# dcb_lite_logic.net
KiCad netlist of a schematic drawn in Altium Designer
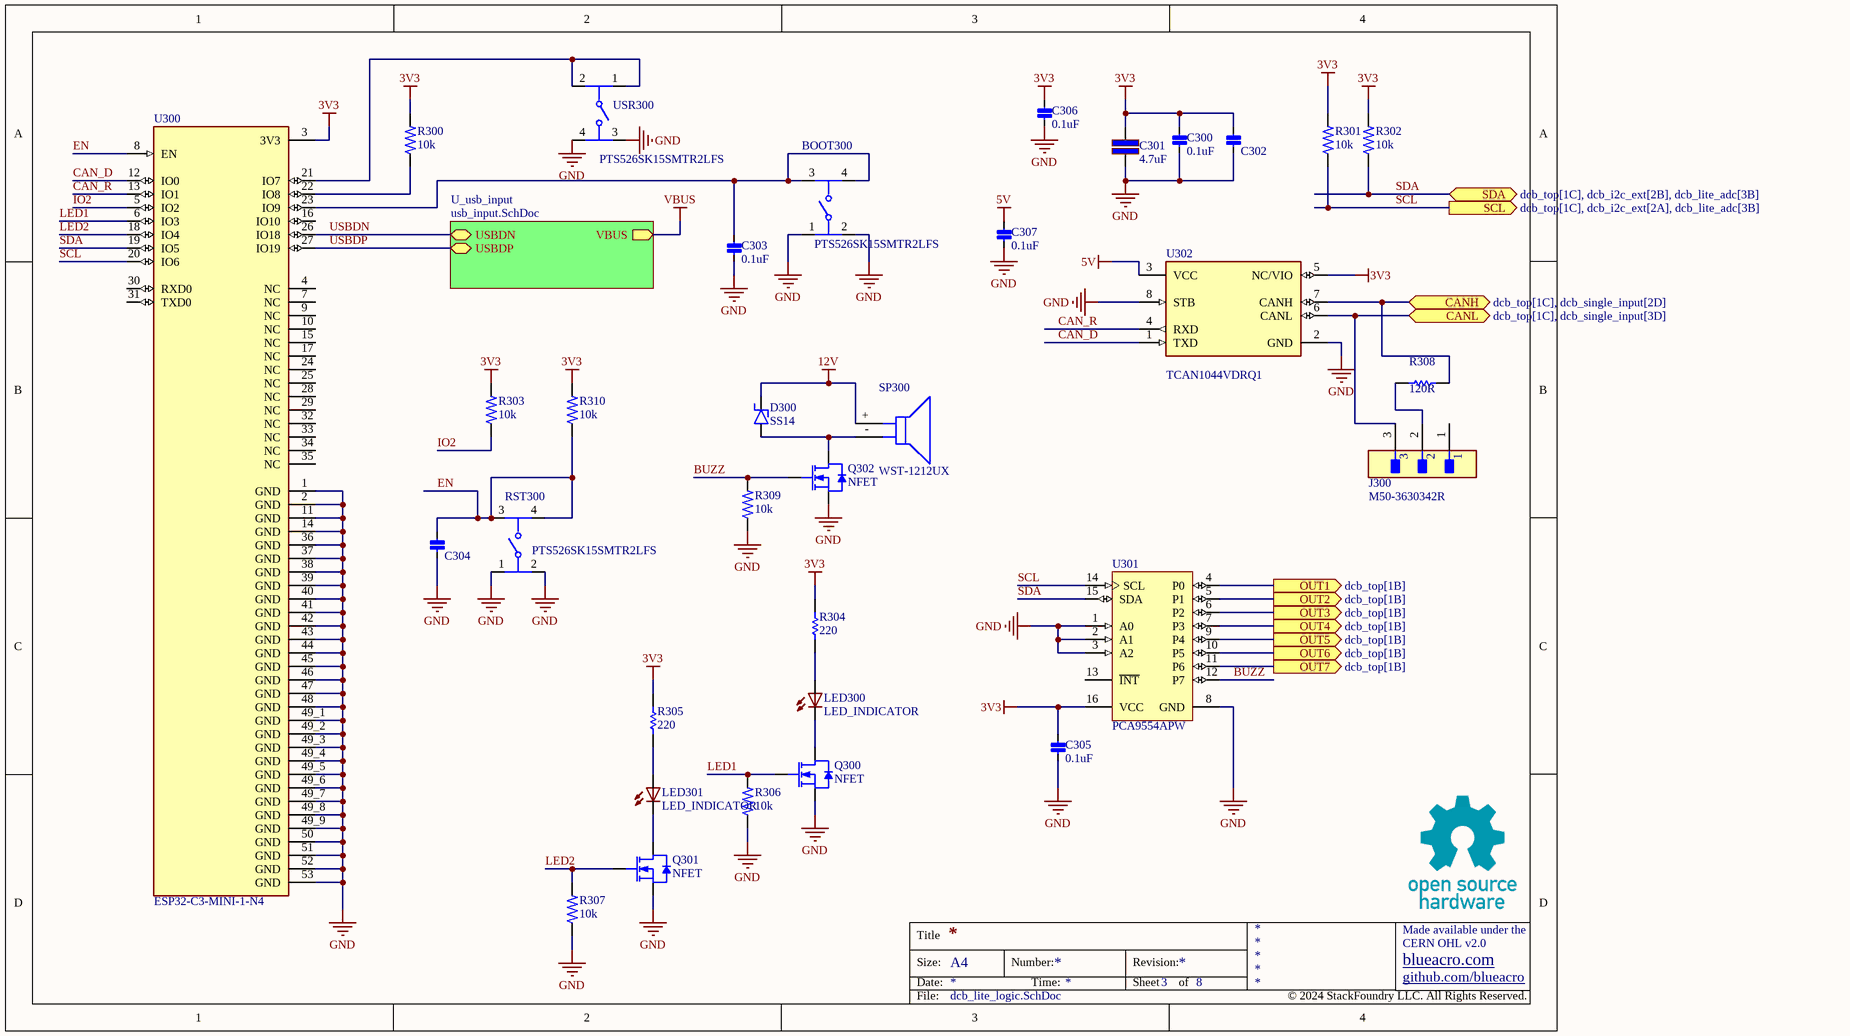
[diagram p0: dcb_lite_logic.SchDoc]

(export (version "E")
  (design (tool "Eeschema 10.0.6"))
  (components
    (comp (ref "BOOT300")
      (value "PTS526SK15SMTR2LFS")
      (footprint "FP-PTS526SK15SMTR2LFS-MFG")
      (description "Switch Tactile N.O. SPST Round Button Gull Wing 0.05A 12VDC 200000Cycles 2.45N SMD T/R")
      (libsource (lib "StackFoundry LLC") (part "b8895f3f4cefb76e1819d2863dba89b"))
    )
    (comp (ref "C300")
      (value "0.1uF")
      (footprint "FP-CL10-IPC_B")
      (description "Cap Ceramic 0.1uF 50V X7R 20% SMD 0603 125C Paper T/R")
      (fields (field (name "VOLTAGE") "50V") (field (name "Comment") "CAP 0.1uF 50V X7R 0603"))
      (libsource (lib "StackFoundry LLC") (part "C-EU"))
    )
    (comp (ref "C301")
      (value "4.7uF")
      (footprint "CAPC3225X20N")
      (description "CAP CER 4.7UF 50V X7R 1210")
      (fields (field (name "VOLTAGE") "50V") (field (name "TOLERANCE") "10%"))
      (libsource (lib "StackFoundry LLC") (part "4.7uF"))
    )
    (comp (ref "C302")
      (value "CAP 1uF 10V X7R 0603")
      (footprint "FP-CL10-IPC_B")
      (description "Cap Ceramic 1uF 10V X7R 10% SMD 0603 125C Paper T/R")
      (libsource (lib "StackFoundry LLC") (part "C-EU"))
    )
    (comp (ref "C303")
      (value "0.1uF")
      (footprint "FP-CL10-IPC_B")
      (description "Cap Ceramic 0.1uF 50V X7R 20% SMD 0603 125C Paper T/R")
      (fields (field (name "VOLTAGE") "50V") (field (name "Comment") "CAP 0.1uF 50V X7R 0603"))
      (libsource (lib "StackFoundry LLC") (part "C-EU"))
    )
    (comp (ref "C304")
      (value "CAP 1uF 10V X7R 0603")
      (footprint "FP-CL10-IPC_B")
      (description "Cap Ceramic 1uF 10V X7R 10% SMD 0603 125C Paper T/R")
      (libsource (lib "StackFoundry LLC") (part "C-EU"))
    )
    (comp (ref "C305")
      (value "0.1uF")
      (footprint "FP-CL10-IPC_B")
      (description "Cap Ceramic 0.1uF 50V X7R 20% SMD 0603 125C Paper T/R")
      (fields (field (name "VOLTAGE") "50V") (field (name "Comment") "CAP 0.1uF 50V X7R 0603"))
      (libsource (lib "StackFoundry LLC") (part "C-EU"))
    )
    (comp (ref "C306")
      (value "0.1uF")
      (footprint "FP-CL10-IPC_B")
      (description "Cap Ceramic 0.1uF 50V X7R 20% SMD 0603 125C Paper T/R")
      (fields (field (name "VOLTAGE") "50V") (field (name "Comment") "CAP 0.1uF 50V X7R 0603"))
      (libsource (lib "StackFoundry LLC") (part "C-EU"))
    )
    (comp (ref "C307")
      (value "0.1uF")
      (footprint "FP-CL10-IPC_B")
      (description "Cap Ceramic 0.1uF 50V X7R 20% SMD 0603 125C Paper T/R")
      (fields (field (name "VOLTAGE") "50V") (field (name "Comment") "CAP 0.1uF 50V X7R 0603"))
      (libsource (lib "StackFoundry LLC") (part "C-EU"))
    )
    (comp (ref "D300")
      (value "SS14")
      (footprint "SMA")
      (libsource (lib "StackFoundry LLC") (part "DIODE_SCHOTTKY"))
    )
    (comp (ref "J300")
      (value "M50-3630342R")
      (footprint "FP-M50-3630342R-MFG")
      (description "3 Pos. Male SIL Vertical SMT Conn. RoHS Compliant: Yes")
      (libsource (lib "StackFoundry LLC") (part "0d3f023dd272f625e17a2be33dea85f"))
    )
    (comp (ref "LED300")
      (value "LED_INDICATOR")
      (footprint "LED5MM")
      (libsource (lib "StackFoundry LLC") (part "LED_INDICATOR"))
    )
    (comp (ref "LED301")
      (value "LED_INDICATOR")
      (footprint "LED5MM")
      (libsource (lib "StackFoundry LLC") (part "LED_INDICATOR"))
    )
    (comp (ref "Q300")
      (value "NFET")
      (footprint "SOT23-3")
      (libsource (lib "StackFoundry LLC") (part "NFET"))
    )
    (comp (ref "Q301")
      (value "NFET")
      (footprint "SOT23-3")
      (libsource (lib "StackFoundry LLC") (part "NFET"))
    )
    (comp (ref "Q302")
      (value "NFET")
      (footprint "SOT23-3")
      (libsource (lib "StackFoundry LLC") (part "NFET"))
    )
    (comp (ref "R300")
      (value "10k")
      (footprint "RESC1608-IPC-ML")
      (description "Res General Purpose Thick Film 0603 10K Ohm 1% 1/10W ±100ppm/°C Molded SMD Paper T/R")
      (fields (field (name "Comment") "10K 0603 1%"))
      (libsource (lib "StackFoundry LLC") (part "R-US"))
    )
    (comp (ref "R301")
      (value "10k")
      (footprint "RESC1608-IPC-ML")
      (description "Res General Purpose Thick Film 0603 10K Ohm 1% 1/10W ±100ppm/°C Molded SMD Paper T/R")
      (fields (field (name "Comment") "10K 0603 1%"))
      (libsource (lib "StackFoundry LLC") (part "R-US"))
    )
    (comp (ref "R302")
      (value "10k")
      (footprint "RESC1608-IPC-ML")
      (description "Res General Purpose Thick Film 0603 10K Ohm 1% 1/10W ±100ppm/°C Molded SMD Paper T/R")
      (fields (field (name "Comment") "10K 0603 1%"))
      (libsource (lib "StackFoundry LLC") (part "R-US"))
    )
    (comp (ref "R303")
      (value "10k")
      (footprint "RESC1608-IPC-ML")
      (description "Res General Purpose Thick Film 0603 10K Ohm 1% 1/10W ±100ppm/°C Molded SMD Paper T/R")
      (fields (field (name "Comment") "10K 0603 1%"))
      (libsource (lib "StackFoundry LLC") (part "R-US"))
    )
    (comp (ref "R304")
      (value "220")
      (footprint "RESC1608-IPC-ML")
      (fields (field (name "TOLERANCE") "5%") (field (name "Comment") "220R 0603 5%"))
      (libsource (lib "StackFoundry LLC") (part "RES-2"))
    )
    (comp (ref "R305")
      (value "220")
      (footprint "RESC1608-IPC-ML")
      (fields (field (name "TOLERANCE") "5%") (field (name "Comment") "220R 0603 5%"))
      (libsource (lib "StackFoundry LLC") (part "RES-2"))
    )
    (comp (ref "R306")
      (value "10k")
      (footprint "RESC1608-IPC-ML")
      (description "Res General Purpose Thick Film 0603 10K Ohm 1% 1/10W ±100ppm/°C Molded SMD Paper T/R")
      (fields (field (name "Comment") "10K 0603 1%"))
      (libsource (lib "StackFoundry LLC") (part "R-US"))
    )
    (comp (ref "R307")
      (value "10k")
      (footprint "RESC1608-IPC-ML")
      (description "Res General Purpose Thick Film 0603 10K Ohm 1% 1/10W ±100ppm/°C Molded SMD Paper T/R")
      (fields (field (name "Comment") "10K 0603 1%"))
      (libsource (lib "StackFoundry LLC") (part "R-US"))
    )
    (comp (ref "R308")
      (value "120R")
      (footprint "RESC3225X70X50LL20T20")
      (description "SMD Chip Resistor, 120 Ohm, ± 5%, 500 mW, 1210 [3225 Metric], Thick Film, General Purpose")
      (fields (field (name "TOLERANCE") "5%") (field (name "Comment") "120R 1210 5%"))
      (libsource (lib "StackFoundry LLC") (part "RES"))
    )
    (comp (ref "R309")
      (value "10k")
      (footprint "RESC1608-IPC-ML")
      (description "Res General Purpose Thick Film 0603 10K Ohm 1% 1/10W ±100ppm/°C Molded SMD Paper T/R")
      (fields (field (name "Comment") "10K 0603 1%"))
      (libsource (lib "StackFoundry LLC") (part "R-US"))
    )
    (comp (ref "R310")
      (value "10k")
      (footprint "RESC1608-IPC-ML")
      (description "Res General Purpose Thick Film 0603 10K Ohm 1% 1/10W ±100ppm/°C Molded SMD Paper T/R")
      (fields (field (name "Comment") "10K 0603 1%"))
      (libsource (lib "StackFoundry LLC") (part "R-US"))
    )
    (comp (ref "RST300")
      (value "PTS526SK15SMTR2LFS")
      (footprint "FP-PTS526SK15SMTR2LFS-MFG")
      (description "Switch Tactile N.O. SPST Round Button Gull Wing 0.05A 12VDC 200000Cycles 2.45N SMD T/R")
      (libsource (lib "StackFoundry LLC") (part "b8895f3f4cefb76e1819d2863dba89b"))
    )
    (comp (ref "SP300")
      (value "WST-1212UX")
      (footprint "WST-1212UX-Footprint-1")
      (description "Audio Magnetic Xdcr 9-15V Th")
      (libsource (lib "StackFoundry LLC") (part "WST-1212UX-Symbol-1"))
    )
    (comp (ref "U300")
      (value "ESP32-C3-MINI-1-N4")
      (footprint "XCVR_ESP32-C3-MINI-1-N4")
      (fields (field (name "MF") "Espressif Systems"))
      (libsource (lib "StackFoundry LLC") (part "ESP32-C3-MINI-1-N4"))
    )
    (comp (ref "U301")
      (value "PCA9554APW")
      (footprint "PW0016A_L")
      (description "I2C/SMBus Interface 100kHz/400kHz 5.5V 16-Pin TSSOP Tube / IC I/O EXPANDER I2C 8B 16TSSOP")
      (libsource (lib "StackFoundry LLC") (part "TI-PCA9554A-TSSOP_PW-16"))
    )
    (comp (ref "U302")
      (value "TCAN1044VDRQ1")
      (footprint "FP-D0008A-IPC_B")
      (description "R-PDSO-G8 TCAN1044 Tape & Reel (TR) CAN interface transceiver 100mV 4.905mm 5Mbps -40C~125C TA")
      (libsource (lib "StackFoundry LLC") (part "37286c69b09cf1f90c6308c73223085"))
    )
    (comp (ref "USR300")
      (value "PTS526SK15SMTR2LFS")
      (footprint "FP-PTS526SK15SMTR2LFS-MFG")
      (description "Switch Tactile N.O. SPST Round Button Gull Wing 0.05A 12VDC 200000Cycles 2.45N SMD T/R")
      (libsource (lib "StackFoundry LLC") (part "b8895f3f4cefb76e1819d2863dba89b"))
    )
  )
  (nets
    (net (code "1") (name "/BUZZ") (class "Default")
      (node (ref "Q302") (pin "1") (pinfunction "G_1") (pintype "passive"))
      (node (ref "R309") (pin "2") (pinfunction "2_2") (pintype "passive"))
      (node (ref "U301") (pin "12") (pinfunction "P7_12") (pintype "bidirectional"))
    )
    (net (code "2") (name "/CANH") (class "Default")
      (node (ref "R308") (pin "2") (pinfunction "2_2") (pintype "passive"))
      (node (ref "U302") (pin "7") (pinfunction "CANH_7") (pintype "bidirectional"))
    )
    (net (code "3") (name "/CANL") (class "Default")
      (node (ref "J300") (pin "3") (pinfunction "3_3") (pintype "passive"))
      (node (ref "U302") (pin "6") (pinfunction "CANL_6") (pintype "bidirectional"))
    )
    (net (code "4") (name "/CAN_D") (class "Default")
      (node (ref "U300") (pin "12") (pinfunction "IO0_12") (pintype "bidirectional"))
      (node (ref "U302") (pin "1") (pinfunction "TXD_1") (pintype "input"))
    )
    (net (code "5") (name "/CAN_R") (class "Default")
      (node (ref "U300") (pin "13") (pinfunction "IO1_13") (pintype "bidirectional"))
      (node (ref "U302") (pin "4") (pinfunction "RXD_4") (pintype "output"))
    )
    (net (code "6") (name "/EN") (class "Default")
      (node (ref "C304") (pin "1") (pinfunction "1_1") (pintype "passive"))
      (node (ref "R310") (pin "1") (pinfunction "1_1") (pintype "passive"))
      (node (ref "RST300") (pin "3") (pinfunction "3_3") (pintype "passive"))
      (node (ref "RST300") (pin "4") (pinfunction "4_4") (pintype "passive"))
      (node (ref "U300") (pin "8") (pinfunction "EN_8") (pintype "input"))
    )
    (net (code "7") (name "/IO2") (class "Default")
      (node (ref "R303") (pin "1") (pinfunction "1_1") (pintype "passive"))
      (node (ref "U300") (pin "5") (pinfunction "IO2_5") (pintype "bidirectional"))
    )
    (net (code "8") (name "/LED1") (class "Default")
      (node (ref "Q300") (pin "1") (pinfunction "G_1") (pintype "passive"))
      (node (ref "R306") (pin "2") (pinfunction "2_2") (pintype "passive"))
      (node (ref "U300") (pin "6") (pinfunction "IO3_6") (pintype "bidirectional"))
    )
    (net (code "9") (name "/LED2") (class "Default")
      (node (ref "Q301") (pin "1") (pinfunction "G_1") (pintype "passive"))
      (node (ref "R307") (pin "2") (pinfunction "2_2") (pintype "passive"))
      (node (ref "U300") (pin "18") (pinfunction "IO4_18") (pintype "bidirectional"))
    )
    (net (code "10") (name "/OUT1") (class "Default")
      (node (ref "U301") (pin "4") (pinfunction "P0_4") (pintype "bidirectional"))
    )
    (net (code "11") (name "/OUT2") (class "Default")
      (node (ref "U301") (pin "5") (pinfunction "P1_5") (pintype "bidirectional"))
    )
    (net (code "12") (name "/OUT3") (class "Default")
      (node (ref "U301") (pin "6") (pinfunction "P2_6") (pintype "bidirectional"))
    )
    (net (code "13") (name "/OUT4") (class "Default")
      (node (ref "U301") (pin "7") (pinfunction "P3_7") (pintype "bidirectional"))
    )
    (net (code "14") (name "/OUT5") (class "Default")
      (node (ref "U301") (pin "9") (pinfunction "P4_9") (pintype "bidirectional"))
    )
    (net (code "15") (name "/OUT6") (class "Default")
      (node (ref "U301") (pin "10") (pinfunction "P5_10") (pintype "bidirectional"))
    )
    (net (code "16") (name "/OUT7") (class "Default")
      (node (ref "U301") (pin "11") (pinfunction "P6_11") (pintype "bidirectional"))
    )
    (net (code "17") (name "/SCL") (class "Default")
      (node (ref "R301") (pin "1") (pinfunction "1_1") (pintype "passive"))
      (node (ref "U300") (pin "20") (pinfunction "IO6_20") (pintype "bidirectional"))
      (node (ref "U301") (pin "14") (pinfunction "SCL_14") (pintype "input"))
    )
    (net (code "18") (name "/SDA") (class "Default")
      (node (ref "R302") (pin "1") (pinfunction "1_1") (pintype "passive"))
      (node (ref "U300") (pin "19") (pinfunction "IO5_19") (pintype "bidirectional"))
      (node (ref "U301") (pin "15") (pinfunction "SDA_15") (pintype "bidirectional"))
    )
    (net (code "19") (name "/USBDN") (class "Default")
      (node (ref "U300") (pin "26") (pinfunction "IO18_26") (pintype "bidirectional"))
    )
    (net (code "20") (name "/USBDP") (class "Default")
      (node (ref "U300") (pin "27") (pinfunction "IO19_27") (pintype "bidirectional"))
    )
    (net (code "21") (name "3V3") (class "Default")
      (node (ref "C300") (pin "1") (pinfunction "1_1") (pintype "passive"))
      (node (ref "C301") (pin "2") (pintype "passive"))
      (node (ref "C302") (pin "1") (pinfunction "1_1") (pintype "passive"))
      (node (ref "C305") (pin "1") (pinfunction "1_1") (pintype "passive"))
      (node (ref "C306") (pin "1") (pinfunction "1_1") (pintype "passive"))
      (node (ref "R300") (pin "2") (pinfunction "2_2") (pintype "passive"))
      (node (ref "R301") (pin "2") (pinfunction "2_2") (pintype "passive"))
      (node (ref "R302") (pin "2") (pinfunction "2_2") (pintype "passive"))
      (node (ref "R303") (pin "2") (pinfunction "2_2") (pintype "passive"))
      (node (ref "R304") (pin "2") (pinfunction "2_2") (pintype "passive"))
      (node (ref "R305") (pin "2") (pinfunction "2_2") (pintype "passive"))
      (node (ref "R310") (pin "2") (pinfunction "2_2") (pintype "passive"))
      (node (ref "U300") (pin "3") (pinfunction "3V3_3") (pintype "power_in"))
      (node (ref "U301") (pin "16") (pinfunction "VCC_16") (pintype "power_in"))
      (node (ref "U302") (pin "5") (pinfunction "NC/VIO_5") (pintype "bidirectional"))
    )
    (net (code "22") (name "5V") (class "Default")
      (node (ref "C307") (pin "1") (pinfunction "1_1") (pintype "passive"))
      (node (ref "U302") (pin "3") (pinfunction "VCC_3") (pintype "power_in"))
    )
    (net (code "23") (name "12V") (class "Default")
      (node (ref "D300") (pin "K") (pinfunction "K_K") (pintype "power_in"))
      (node (ref "SP300") (pin "+") (pinfunction "+_+") (pintype "passive"))
    )
    (net (code "24") (name "GND") (class "Default")
      (node (ref "BOOT300") (pin "1") (pinfunction "1_1") (pintype "passive"))
      (node (ref "BOOT300") (pin "2") (pinfunction "2_2") (pintype "passive"))
      (node (ref "C300") (pin "2") (pinfunction "2_2") (pintype "passive"))
      (node (ref "C301") (pin "1") (pintype "passive"))
      (node (ref "C302") (pin "2") (pinfunction "2_2") (pintype "passive"))
      (node (ref "C303") (pin "2") (pinfunction "2_2") (pintype "passive"))
      (node (ref "C304") (pin "2") (pinfunction "2_2") (pintype "passive"))
      (node (ref "C305") (pin "2") (pinfunction "2_2") (pintype "passive"))
      (node (ref "C306") (pin "2") (pinfunction "2_2") (pintype "passive"))
      (node (ref "C307") (pin "2") (pinfunction "2_2") (pintype "passive"))
      (node (ref "Q300") (pin "2") (pinfunction "S_2") (pintype "passive"))
      (node (ref "Q301") (pin "2") (pinfunction "S_2") (pintype "passive"))
      (node (ref "Q302") (pin "2") (pinfunction "S_2") (pintype "passive"))
      (node (ref "R306") (pin "1") (pinfunction "1_1") (pintype "passive"))
      (node (ref "R307") (pin "1") (pinfunction "1_1") (pintype "passive"))
      (node (ref "R309") (pin "1") (pinfunction "1_1") (pintype "passive"))
      (node (ref "RST300") (pin "1") (pinfunction "1_1") (pintype "passive"))
      (node (ref "RST300") (pin "2") (pinfunction "2_2") (pintype "passive"))
      (node (ref "U300") (pin "1") (pinfunction "GND_1") (pintype "power_in"))
      (node (ref "U300") (pin "11") (pinfunction "GND_11") (pintype "power_in"))
      (node (ref "U300") (pin "14") (pinfunction "GND_14") (pintype "power_in"))
      (node (ref "U300") (pin "2") (pinfunction "GND_2") (pintype "power_in"))
      (node (ref "U300") (pin "36") (pinfunction "GND_36") (pintype "power_in"))
      (node (ref "U300") (pin "37") (pinfunction "GND_37") (pintype "power_in"))
      (node (ref "U300") (pin "38") (pinfunction "GND_38") (pintype "power_in"))
      (node (ref "U300") (pin "39") (pinfunction "GND_39") (pintype "power_in"))
      (node (ref "U300") (pin "40") (pinfunction "GND_40") (pintype "power_in"))
      (node (ref "U300") (pin "41") (pinfunction "GND_41") (pintype "power_in"))
      (node (ref "U300") (pin "42") (pinfunction "GND_42") (pintype "power_in"))
      (node (ref "U300") (pin "43") (pinfunction "GND_43") (pintype "power_in"))
      (node (ref "U300") (pin "44") (pinfunction "GND_44") (pintype "power_in"))
      (node (ref "U300") (pin "45") (pinfunction "GND_45") (pintype "power_in"))
      (node (ref "U300") (pin "46") (pinfunction "GND_46") (pintype "power_in"))
      (node (ref "U300") (pin "47") (pinfunction "GND_47") (pintype "power_in"))
      (node (ref "U300") (pin "48") (pinfunction "GND_48") (pintype "power_in"))
      (node (ref "U300") (pin "49_1") (pinfunction "GND_49_1") (pintype "power_in"))
      (node (ref "U300") (pin "49_2") (pinfunction "GND_49_2") (pintype "power_in"))
      (node (ref "U300") (pin "49_3") (pinfunction "GND_49_3") (pintype "power_in"))
      (node (ref "U300") (pin "49_4") (pinfunction "GND_49_4") (pintype "power_in"))
      (node (ref "U300") (pin "49_5") (pinfunction "GND_49_5") (pintype "power_in"))
      (node (ref "U300") (pin "49_6") (pinfunction "GND_49_6") (pintype "power_in"))
      (node (ref "U300") (pin "49_7") (pinfunction "GND_49_7") (pintype "power_in"))
      (node (ref "U300") (pin "49_8") (pinfunction "GND_49_8") (pintype "power_in"))
      (node (ref "U300") (pin "49_9") (pinfunction "GND_49_9") (pintype "power_in"))
      (node (ref "U300") (pin "50") (pinfunction "GND_50") (pintype "power_in"))
      (node (ref "U300") (pin "51") (pinfunction "GND_51") (pintype "power_in"))
      (node (ref "U300") (pin "52") (pinfunction "GND_52") (pintype "power_in"))
      (node (ref "U300") (pin "53") (pinfunction "GND_53") (pintype "power_in"))
      (node (ref "U301") (pin "1") (pinfunction "A0_1") (pintype "input"))
      (node (ref "U301") (pin "2") (pinfunction "A1_2") (pintype "input"))
      (node (ref "U301") (pin "3") (pinfunction "A2_3") (pintype "input"))
      (node (ref "U301") (pin "8") (pinfunction "GND_8") (pintype "power_in"))
      (node (ref "U302") (pin "2") (pinfunction "GND_2") (pintype "power_in"))
      (node (ref "U302") (pin "8") (pinfunction "STB_8") (pintype "input"))
      (node (ref "USR300") (pin "3") (pinfunction "3_3") (pintype "passive"))
      (node (ref "USR300") (pin "4") (pinfunction "4_4") (pintype "passive"))
    )
    (net (code "25") (name "Net-(J300-Pad2)") (class "Default")
      (node (ref "J300") (pin "2") (pinfunction "2_2") (pintype "passive"))
      (node (ref "R308") (pin "1") (pinfunction "1_1") (pintype "passive"))
    )
    (net (code "26") (name "Net-(LED300-PadA)") (class "Default")
      (node (ref "LED300") (pin "A") (pinfunction "A_A") (pintype "passive"))
      (node (ref "R304") (pin "1") (pinfunction "1_1") (pintype "passive"))
    )
    (net (code "27") (name "Net-(LED301-PadA)") (class "Default")
      (node (ref "LED301") (pin "A") (pinfunction "A_A") (pintype "passive"))
      (node (ref "R305") (pin "1") (pinfunction "1_1") (pintype "passive"))
    )
    (net (code "28") (name "Net-(Q300-D)") (class "Default")
      (node (ref "LED300") (pin "C") (pinfunction "C_C") (pintype "passive"))
      (node (ref "Q300") (pin "3") (pinfunction "D_3") (pintype "passive"))
    )
    (net (code "29") (name "Net-(Q301-D)") (class "Default")
      (node (ref "LED301") (pin "C") (pinfunction "C_C") (pintype "passive"))
      (node (ref "Q301") (pin "3") (pinfunction "D_3") (pintype "passive"))
    )
    (net (code "30") (name "Net-(Q302-D)") (class "Default")
      (node (ref "D300") (pin "A") (pinfunction "A_A") (pintype "power_in"))
      (node (ref "Q302") (pin "3") (pinfunction "D_3") (pintype "passive"))
      (node (ref "SP300") (pin "-") (pinfunction "-_-") (pintype "passive"))
    )
    (net (code "31") (name "Net-(U300-IO7)") (class "Default")
      (node (ref "U300") (pin "21") (pinfunction "IO7_21") (pintype "bidirectional"))
      (node (ref "USR300") (pin "1") (pinfunction "1_1") (pintype "passive"))
      (node (ref "USR300") (pin "2") (pinfunction "2_2") (pintype "passive"))
    )
    (net (code "32") (name "Net-(U300-IO8)") (class "Default")
      (node (ref "R300") (pin "1") (pinfunction "1_1") (pintype "passive"))
      (node (ref "U300") (pin "22") (pinfunction "IO8_22") (pintype "bidirectional"))
    )
    (net (code "33") (name "Net-(U300-IO9)") (class "Default")
      (node (ref "BOOT300") (pin "3") (pinfunction "3_3") (pintype "passive"))
      (node (ref "BOOT300") (pin "4") (pinfunction "4_4") (pintype "passive"))
      (node (ref "C303") (pin "1") (pinfunction "1_1") (pintype "passive"))
      (node (ref "U300") (pin "23") (pinfunction "IO9_23") (pintype "bidirectional"))
    )
    (net (code "35") (name "unconnected-(J300-Pad1)") (class "Default")
      (node (ref "J300") (pin "1") (pinfunction "1_1") (pintype "passive"))
    )
    (net (code "36") (name "unconnected-(U300-IO10-Pad16)") (class "Default")
      (node (ref "U300") (pin "16") (pinfunction "IO10_16") (pintype "bidirectional"))
    )
    (net (code "37") (name "unconnected-(U300-NC-Pad4)") (class "Default")
      (node (ref "U300") (pin "4") (pinfunction "NC_4") (pintype "passive"))
    )
    (net (code "38") (name "unconnected-(U300-NC-Pad7)") (class "Default")
      (node (ref "U300") (pin "7") (pinfunction "NC_7") (pintype "passive"))
    )
    (net (code "39") (name "unconnected-(U300-NC-Pad9)") (class "Default")
      (node (ref "U300") (pin "9") (pinfunction "NC_9") (pintype "passive"))
    )
    (net (code "40") (name "unconnected-(U300-NC-Pad10)") (class "Default")
      (node (ref "U300") (pin "10") (pinfunction "NC_10") (pintype "passive"))
    )
    (net (code "41") (name "unconnected-(U300-NC-Pad15)") (class "Default")
      (node (ref "U300") (pin "15") (pinfunction "NC_15") (pintype "passive"))
    )
    (net (code "42") (name "unconnected-(U300-NC-Pad17)") (class "Default")
      (node (ref "U300") (pin "17") (pinfunction "NC_17") (pintype "passive"))
    )
    (net (code "43") (name "unconnected-(U300-NC-Pad24)") (class "Default")
      (node (ref "U300") (pin "24") (pinfunction "NC_24") (pintype "passive"))
    )
    (net (code "44") (name "unconnected-(U300-NC-Pad25)") (class "Default")
      (node (ref "U300") (pin "25") (pinfunction "NC_25") (pintype "passive"))
    )
    (net (code "45") (name "unconnected-(U300-NC-Pad28)") (class "Default")
      (node (ref "U300") (pin "28") (pinfunction "NC_28") (pintype "passive"))
    )
    (net (code "46") (name "unconnected-(U300-NC-Pad29)") (class "Default")
      (node (ref "U300") (pin "29") (pinfunction "NC_29") (pintype "passive"))
    )
    (net (code "47") (name "unconnected-(U300-NC-Pad32)") (class "Default")
      (node (ref "U300") (pin "32") (pinfunction "NC_32") (pintype "passive"))
    )
    (net (code "48") (name "unconnected-(U300-NC-Pad33)") (class "Default")
      (node (ref "U300") (pin "33") (pinfunction "NC_33") (pintype "passive"))
    )
    (net (code "49") (name "unconnected-(U300-NC-Pad34)") (class "Default")
      (node (ref "U300") (pin "34") (pinfunction "NC_34") (pintype "passive"))
    )
    (net (code "50") (name "unconnected-(U300-NC-Pad35)") (class "Default")
      (node (ref "U300") (pin "35") (pinfunction "NC_35") (pintype "passive"))
    )
    (net (code "51") (name "unconnected-(U300-RXD0-Pad30)") (class "Default")
      (node (ref "U300") (pin "30") (pinfunction "RXD0_30") (pintype "bidirectional"))
    )
    (net (code "52") (name "unconnected-(U300-TXD0-Pad31)") (class "Default")
      (node (ref "U300") (pin "31") (pinfunction "TXD0_31") (pintype "bidirectional"))
    )
    (net (code "53") (name "unconnected-(U301-~{INT}-Pad13)") (class "Default")
      (node (ref "U301") (pin "13") (pinfunction "~{INT}_13") (pintype "open_collector"))
    )
  )
)
